# DVI.net
KiCad netlist of a schematic drawn in Altium Designer
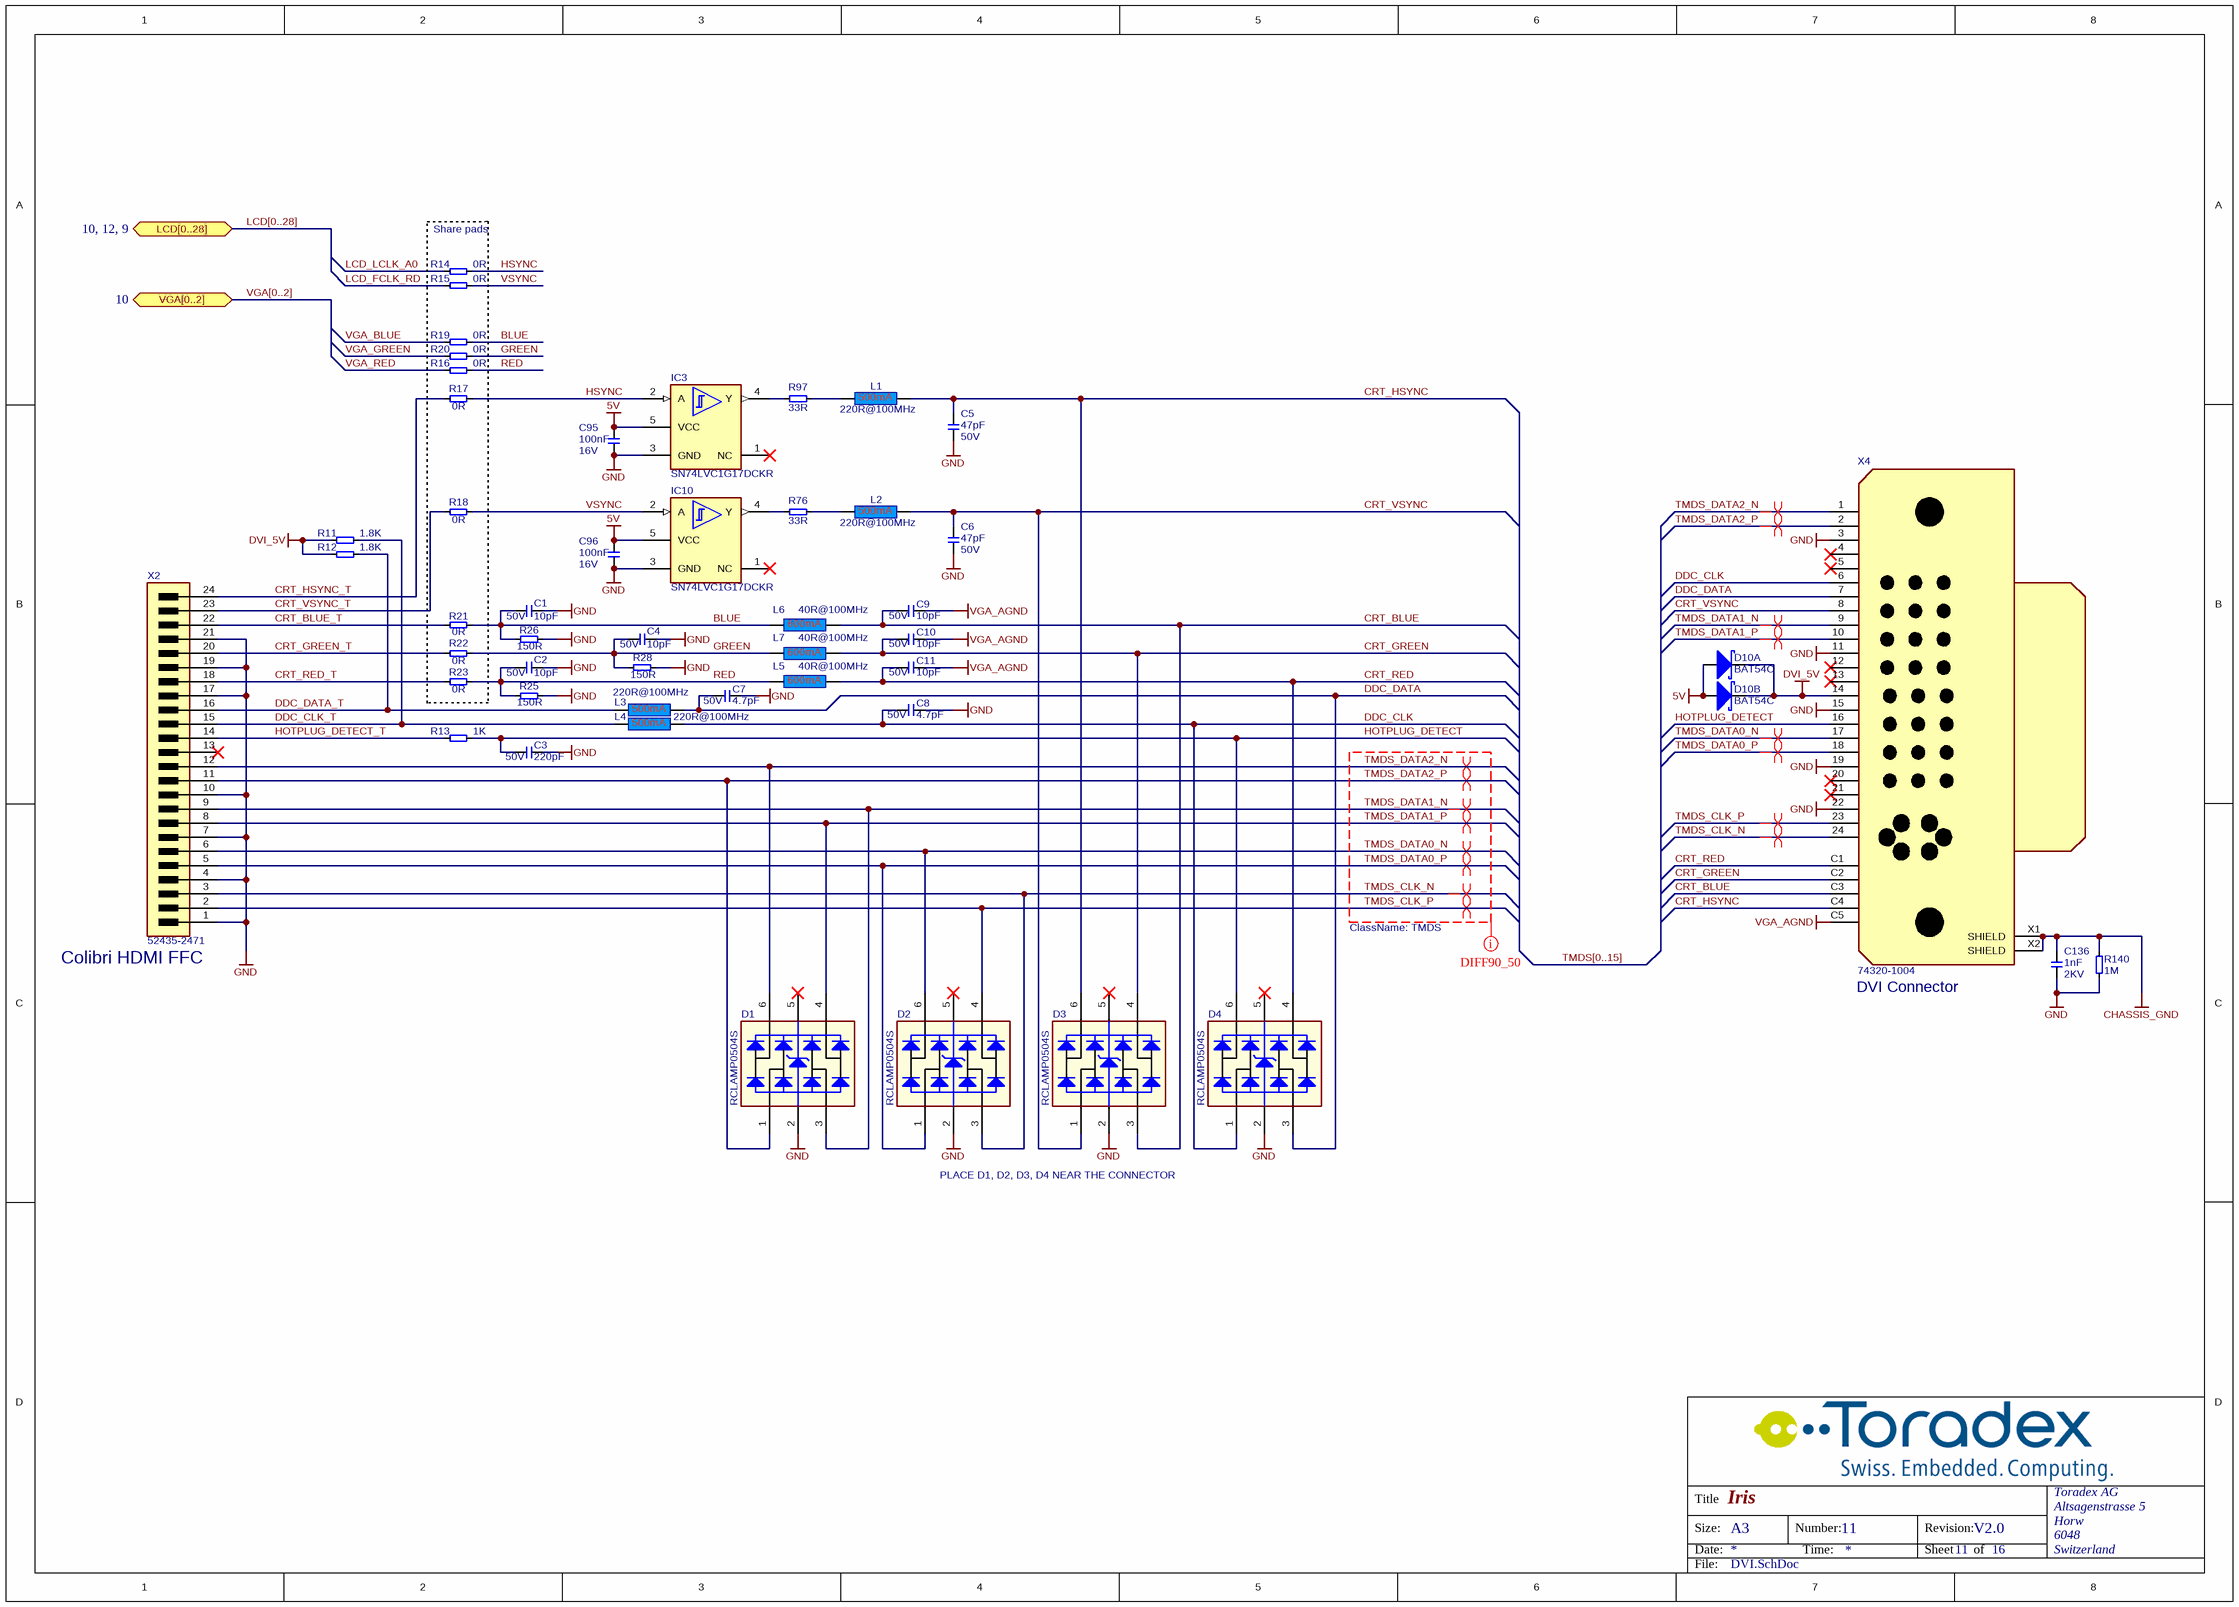
[diagram p0: DVI.SchDoc]

(export (version "E")
  (design (tool "Eeschema 10.0.6"))
  (components
    (comp (ref "C1")
      (value "10pF")
      (footprint "CAPC1005X60N")
      (description "Capacitor Ceramic NP0 10pF 50V 10% 0402")
      (fields (field (name "TOLERANCE") "10%") (field (name "RATING") "50V"))
      (libsource (lib "Iris") (part "C-NP0-10pF-50V-10%-0402"))
    )
    (comp (ref "C2")
      (value "10pF")
      (footprint "CAPC1005X60N")
      (description "Capacitor Ceramic NP0 10pF 50V 10% 0402")
      (fields (field (name "TOLERANCE") "10%") (field (name "RATING") "50V"))
      (libsource (lib "Iris") (part "C-NP0-10pF-50V-10%-0402"))
    )
    (comp (ref "C3")
      (value "220pF")
      (footprint "CAPC1005X60N")
      (description "Capacitor Ceramic X7R 220pF 50V 10% 0402")
      (fields (field (name "TOLERANCE") "10%") (field (name "RATING") "50V"))
      (libsource (lib "Iris") (part "C-X7R-220pF-50V-10%-0402"))
    )
    (comp (ref "C4")
      (value "10pF")
      (footprint "CAPC1005X60N")
      (description "Capacitor Ceramic NP0 10pF 50V 10% 0402")
      (fields (field (name "TOLERANCE") "10%") (field (name "RATING") "50V"))
      (libsource (lib "Iris") (part "C-NP0-10pF-50V-10%-0402"))
    )
    (comp (ref "C5")
      (value "47pF")
      (footprint "CAPC1005X60N")
      (description "Capacitor Ceramic NP0 47pF 50V 5% 0402")
      (fields (field (name "TOLERANCE") "5%") (field (name "RATING") "50V"))
      (libsource (lib "Iris") (part "C-NP0-47pF-50V-5%-0402"))
    )
    (comp (ref "C6")
      (value "47pF")
      (footprint "CAPC1005X60N")
      (description "Capacitor Ceramic NP0 47pF 50V 5% 0402")
      (fields (field (name "TOLERANCE") "5%") (field (name "RATING") "50V"))
      (libsource (lib "Iris") (part "C-NP0-47pF-50V-5%-0402"))
    )
    (comp (ref "C7")
      (value "4.7pF")
      (footprint "CAPC1005X60N")
      (description "Capacitor Ceramic NP0  4.7pF 50V 10% 0402")
      (fields (field (name "TOLERANCE") "10%") (field (name "RATING") "50V"))
      (libsource (lib "Iris") (part "C-NP0-4.7pF-50V-10%-0402"))
    )
    (comp (ref "C8")
      (value "4.7pF")
      (footprint "CAPC1005X60N")
      (description "Capacitor Ceramic NP0  4.7pF 50V 10% 0402")
      (fields (field (name "TOLERANCE") "10%") (field (name "RATING") "50V"))
      (libsource (lib "Iris") (part "C-NP0-4.7pF-50V-10%-0402"))
    )
    (comp (ref "C9")
      (value "10pF")
      (footprint "CAPC1005X60N")
      (description "Capacitor Ceramic NP0 10pF 50V 10% 0402")
      (fields (field (name "TOLERANCE") "10%") (field (name "RATING") "50V"))
      (libsource (lib "Iris") (part "C-NP0-10pF-50V-10%-0402"))
    )
    (comp (ref "C10")
      (value "10pF")
      (footprint "CAPC1005X60N")
      (description "Capacitor Ceramic NP0 10pF 50V 10% 0402")
      (fields (field (name "TOLERANCE") "10%") (field (name "RATING") "50V"))
      (libsource (lib "Iris") (part "C-NP0-10pF-50V-10%-0402"))
    )
    (comp (ref "C11")
      (value "10pF")
      (footprint "CAPC1005X60N")
      (description "Capacitor Ceramic NP0 10pF 50V 10% 0402")
      (fields (field (name "TOLERANCE") "10%") (field (name "RATING") "50V"))
      (libsource (lib "Iris") (part "C-NP0-10pF-50V-10%-0402"))
    )
    (comp (ref "C95")
      (value "100nF")
      (footprint "CAPC1005X60N")
      (description "Capacitor Ceramic X7R 100nF 16V 10% 0402")
      (fields (field (name "TOLERANCE") "10%") (field (name "RATING") "16V"))
      (libsource (lib "Iris") (part "C-X7R-100nF-16V-10%-0402"))
    )
    (comp (ref "C96")
      (value "100nF")
      (footprint "CAPC1005X60N")
      (description "Capacitor Ceramic X7R 100nF 16V 10% 0402")
      (fields (field (name "TOLERANCE") "10%") (field (name "RATING") "16V"))
      (libsource (lib "Iris") (part "C-X7R-100nF-16V-10%-0402"))
    )
    (comp (ref "C136")
      (value "1nF")
      (footprint "T_CAPC1206X180N")
      (description "Capacitor Ceramic X7R 1nF 2KV 10% 1206")
      (fields (field (name "TOLERANCE") "10%") (field (name "RATING") "2KV"))
      (libsource (lib "Iris") (part "C-X7R-1nF-2KV-10%-1206"))
    )
    (comp (ref "D1")
      (value "RCLAMP0504S")
      (footprint "T_SOT95P285X90-6N")
      (description "TVS Array low cap")
      (fields (field (name "MANUFACTURER PART NO.") "RCLAMP0504S"))
      (libsource (lib "Iris") (part "D-Semtech-RClamp0504S"))
    )
    (comp (ref "D2")
      (value "RCLAMP0504S")
      (footprint "T_SOT95P285X90-6N")
      (description "TVS Array low cap")
      (fields (field (name "MANUFACTURER PART NO.") "RCLAMP0504S"))
      (libsource (lib "Iris") (part "D-Semtech-RClamp0504S"))
    )
    (comp (ref "D3")
      (value "RCLAMP0504S")
      (footprint "T_SOT95P285X90-6N")
      (description "TVS Array low cap")
      (fields (field (name "MANUFACTURER PART NO.") "RCLAMP0504S"))
      (libsource (lib "Iris") (part "D-Semtech-RClamp0504S"))
    )
    (comp (ref "D4")
      (value "RCLAMP0504S")
      (footprint "T_SOT95P285X90-6N")
      (description "TVS Array low cap")
      (fields (field (name "MANUFACTURER PART NO.") "RCLAMP0504S"))
      (libsource (lib "Iris") (part "D-Semtech-RClamp0504S"))
    )
    (comp (ref "D10")
      (value "BAT54C")
      (footprint "SOT95P230X110-3N")
      (description "BAT54C Schottky Diode")
      (fields (field (name "MANUFACTURER PART NO.") "BAT54C"))
      (libsource (lib "Iris") (part "D-Philips-BAT54C-Schottky"))
    )
    (comp (ref "IC3")
      (value "SN74LVC1G17DCKR")
      (footprint "SOT65P210X110-5N")
      (description "Schmitt Trigger Buffer, SO-70 package")
      (fields (field (name "MANUFACTURER PART NO.") "SN74LVC1G17DCKR"))
      (libsource (lib "Iris") (part "IC-TI-SN74LVC1G17DCKR"))
    )
    (comp (ref "IC10")
      (value "SN74LVC1G17DCKR")
      (footprint "SOT65P210X110-5N")
      (description "Schmitt Trigger Buffer, SO-70 package")
      (fields (field (name "MANUFACTURER PART NO.") "SN74LVC1G17DCKR"))
      (libsource (lib "Iris") (part "IC-TI-SN74LVC1G17DCKR"))
    )
    (comp (ref "L1")
      (value "220R@100MHz")
      (footprint "INDC1005X55N")
      (description "Ferrite Bead, 220R@100MHz, 500mA, 0402 (1005 metric)")
      (fields (field (name "TOLERANCE") "25%"))
      (libsource (lib "Iris") (part "L-220R@100MHz-500mA-25%-0402"))
    )
    (comp (ref "L2")
      (value "220R@100MHz")
      (footprint "INDC1005X55N")
      (description "Ferrite Bead, 220R@100MHz, 500mA, 0402 (1005 metric)")
      (fields (field (name "TOLERANCE") "25%"))
      (libsource (lib "Iris") (part "L-220R@100MHz-500mA-25%-0402"))
    )
    (comp (ref "L3")
      (value "220R@100MHz")
      (footprint "INDC1005X55N")
      (description "Ferrite Bead, 220R@100MHz, 500mA, 0402 (1005 metric)")
      (fields (field (name "TOLERANCE") "25%"))
      (libsource (lib "Iris") (part "L-220R@100MHz-500mA-25%-0402"))
    )
    (comp (ref "L4")
      (value "220R@100MHz")
      (footprint "INDC1005X55N")
      (description "Ferrite Bead, 220R@100MHz, 500mA, 0402 (1005 metric)")
      (fields (field (name "TOLERANCE") "25%"))
      (libsource (lib "Iris") (part "L-220R@100MHz-500mA-25%-0402"))
    )
    (comp (ref "L5")
      (value "40R@100MHz")
      (footprint "INDC1608X95N")
      (description "40R@100MHz 600mA EMI FILTER")
      (fields (field (name "TOLERANCE") "25%") (field (name "MANUFACTURER PART NO.") "MMZ1608S400A"))
      (libsource (lib "Iris") (part "L-TDK-MMZ1608S400A-40R@100MHz-600mA-25%-0603"))
    )
    (comp (ref "L6")
      (value "40R@100MHz")
      (footprint "INDC1608X95N")
      (description "40R@100MHz 600mA EMI FILTER")
      (fields (field (name "TOLERANCE") "25%") (field (name "MANUFACTURER PART NO.") "MMZ1608S400A"))
      (libsource (lib "Iris") (part "L-TDK-MMZ1608S400A-40R@100MHz-600mA-25%-0603"))
    )
    (comp (ref "L7")
      (value "40R@100MHz")
      (footprint "INDC1608X95N")
      (description "40R@100MHz 600mA EMI FILTER")
      (fields (field (name "TOLERANCE") "25%") (field (name "MANUFACTURER PART NO.") "MMZ1608S400A"))
      (libsource (lib "Iris") (part "L-TDK-MMZ1608S400A-40R@100MHz-600mA-25%-0603"))
    )
    (comp (ref "R11")
      (value "1.8K")
      (footprint "RESC1005X40N")
      (description "Resistor 1.8 Kohm 63mW 5% 0402")
      (fields (field (name "TOLERANCE") "5%"))
      (libsource (lib "Iris") (part "R-1.8KR-63mW-5%-0402"))
    )
    (comp (ref "R12")
      (value "1.8K")
      (footprint "RESC1005X40N")
      (description "Resistor 1.8 Kohm 63mW 5% 0402")
      (fields (field (name "TOLERANCE") "5%"))
      (libsource (lib "Iris") (part "R-1.8KR-63mW-5%-0402"))
    )
    (comp (ref "R13")
      (value "1K")
      (footprint "RESC1005X40N")
      (description "Resistor 1 Kohm 63mW 5% 0402")
      (fields (field (name "TOLERANCE") "5%"))
      (libsource (lib "Iris") (part "R-1KR-63mW-5%-0402"))
    )
    (comp (ref "R14")
      (value "0R")
      (footprint "T_RESC0603X30N")
      (description "Resistor 0 ohm 63mW 5% 0603")
      (fields (field (name "TOLERANCE") "5%"))
      (libsource (lib "Iris") (part "R-0R-63mW-5%-0603"))
    )
    (comp (ref "R15")
      (value "0R")
      (footprint "T_RESC0603X30N")
      (description "Resistor 0 ohm 63mW 5% 0603")
      (fields (field (name "TOLERANCE") "5%"))
      (libsource (lib "Iris") (part "R-0R-63mW-5%-0603"))
    )
    (comp (ref "R16")
      (value "0R")
      (footprint "T_RESC0603X30N")
      (description "Resistor 0 ohm 63mW 5% 0603")
      (fields (field (name "TOLERANCE") "5%"))
      (libsource (lib "Iris") (part "R-0R-63mW-5%-0603"))
    )
    (comp (ref "R17")
      (value "0R")
      (footprint "T_RESC0603X30N")
      (description "Resistor 0 ohm 63mW 5% 0603")
      (fields (field (name "TOLERANCE") "5%"))
      (libsource (lib "Iris") (part "R-0R-63mW-5%-0603"))
    )
    (comp (ref "R18")
      (value "0R")
      (footprint "T_RESC0603X30N")
      (description "Resistor 0 ohm 63mW 5% 0603")
      (fields (field (name "TOLERANCE") "5%"))
      (libsource (lib "Iris") (part "R-0R-63mW-5%-0603"))
    )
    (comp (ref "R19")
      (value "0R")
      (footprint "T_RESC0603X30N")
      (description "Resistor 0 ohm 63mW 5% 0603")
      (fields (field (name "TOLERANCE") "5%"))
      (libsource (lib "Iris") (part "R-0R-63mW-5%-0603"))
    )
    (comp (ref "R20")
      (value "0R")
      (footprint "T_RESC0603X30N")
      (description "Resistor 0 ohm 63mW 5% 0603")
      (fields (field (name "TOLERANCE") "5%"))
      (libsource (lib "Iris") (part "R-0R-63mW-5%-0603"))
    )
    (comp (ref "R21")
      (value "0R")
      (footprint "T_RESC0603X30N")
      (description "Resistor 0 ohm 63mW 5% 0603")
      (fields (field (name "TOLERANCE") "5%"))
      (libsource (lib "Iris") (part "R-0R-63mW-5%-0603"))
    )
    (comp (ref "R22")
      (value "0R")
      (footprint "T_RESC0603X30N")
      (description "Resistor 0 ohm 63mW 5% 0603")
      (fields (field (name "TOLERANCE") "5%"))
      (libsource (lib "Iris") (part "R-0R-63mW-5%-0603"))
    )
    (comp (ref "R23")
      (value "0R")
      (footprint "T_RESC0603X30N")
      (description "Resistor 0 ohm 63mW 5% 0603")
      (fields (field (name "TOLERANCE") "5%"))
      (libsource (lib "Iris") (part "R-0R-63mW-5%-0603"))
    )
    (comp (ref "R25")
      (value "150R")
      (footprint "RESC1005X40N")
      (description "Resistor 150 ohm 63mW 5% 0402")
      (fields (field (name "TOLERANCE") "5%"))
      (libsource (lib "Iris") (part "R-150R-63mW-5%-0402"))
    )
    (comp (ref "R26")
      (value "150R")
      (footprint "RESC1005X40N")
      (description "Resistor 150 ohm 63mW 5% 0402")
      (fields (field (name "TOLERANCE") "5%"))
      (libsource (lib "Iris") (part "R-150R-63mW-5%-0402"))
    )
    (comp (ref "R28")
      (value "150R")
      (footprint "RESC1005X40N")
      (description "Resistor 150 ohm 63mW 5% 0402")
      (fields (field (name "TOLERANCE") "5%"))
      (libsource (lib "Iris") (part "R-150R-63mW-5%-0402"))
    )
    (comp (ref "R76")
      (value "33R")
      (footprint "RESC1005X40N")
      (description "Resistor 33 ohm 63mW 5% 0402")
      (fields (field (name "TOLERANCE") "5%"))
      (libsource (lib "Iris") (part "R-33R-63mW-5%-0402"))
    )
    (comp (ref "R97")
      (value "33R")
      (footprint "RESC1005X40N")
      (description "Resistor 33 ohm 63mW 5% 0402")
      (fields (field (name "TOLERANCE") "5%"))
      (libsource (lib "Iris") (part "R-33R-63mW-5%-0402"))
    )
    (comp (ref "R140")
      (value "1M")
      (footprint "T_RESC0603X30N")
      (description "Resistor 1 Mohm 63mW 5% 0603")
      (fields (field (name "TOLERANCE") "5%"))
      (libsource (lib "Iris") (part "R-1MR-63mW-5%-0603"))
    )
    (comp (ref "X2")
      (value "52435-2471")
      (footprint "T_MOLEX_52435-2471")
      (description "0.50mm Pitch FFC/FPC DVI Connector")
      (fields (field (name "MANUFACTURER PART NO.") "52435-2471"))
      (libsource (lib "Iris") (part "CON-Molex-52435-2471-24-0.5mm"))
    )
    (comp (ref "X4")
      (value "CON-Molex-74320-1004-31")
      (footprint "T_MOLEX_74320-1004")
      (description "DVI Connector")
      (fields (field (name "MANUFACTURER PART NO.") "74320-1004"))
      (libsource (lib "Iris") (part "CON-Molex-74320-1004-31"))
    )
  )
  (nets
    (net (code "49") (name "/BLUE") (class "Default")
      (node (ref "C1") (pin "1") (pinfunction "1_1") (pintype "passive"))
      (node (ref "L6") (pin "1") (pinfunction "1_1") (pintype "passive"))
      (node (ref "R19") (pin "1") (pinfunction "1_1") (pintype "passive"))
      (node (ref "R21") (pin "1") (pinfunction "1_1") (pintype "passive"))
      (node (ref "R26") (pin "1") (pinfunction "1_1") (pintype "passive"))
    )
    (net (code "50") (name "/CRT_BLUE") (class "Default")
      (node (ref "C9") (pin "1") (pinfunction "1_1") (pintype "passive"))
      (node (ref "D3") (pin "3") (pinfunction "3_3") (pintype "power_in"))
      (node (ref "L6") (pin "2") (pinfunction "2_2") (pintype "passive"))
      (node (ref "X4") (pin "C3") (pinfunction "CRT_BLUE_C3") (pintype "passive"))
    )
    (net (code "51") (name "/CRT_BLUE_T") (class "Default")
      (node (ref "R21") (pin "2") (pinfunction "2_2") (pintype "passive"))
      (node (ref "X2") (pin "22") (pinfunction "CRT_BLUE_22") (pintype "passive"))
    )
    (net (code "52") (name "/CRT_GREEN") (class "Default")
      (node (ref "C10") (pin "1") (pinfunction "1_1") (pintype "passive"))
      (node (ref "D3") (pin "4") (pinfunction "4_4") (pintype "power_in"))
      (node (ref "L7") (pin "2") (pinfunction "2_2") (pintype "passive"))
      (node (ref "X4") (pin "C2") (pinfunction "CRT_GREEN_C2") (pintype "passive"))
    )
    (net (code "53") (name "/CRT_GREEN_T") (class "Default")
      (node (ref "R22") (pin "2") (pinfunction "2_2") (pintype "passive"))
      (node (ref "X2") (pin "20") (pinfunction "CRT_GREEN_20") (pintype "passive"))
    )
    (net (code "54") (name "/CRT_HSYNC") (class "Default")
      (node (ref "C5") (pin "1") (pinfunction "1_1") (pintype "passive"))
      (node (ref "D3") (pin "6") (pinfunction "6_6") (pintype "power_in"))
      (node (ref "L1") (pin "2") (pinfunction "2_2") (pintype "passive"))
      (node (ref "X4") (pin "C4") (pinfunction "CRT_HSYNC_C4") (pintype "passive"))
    )
    (net (code "55") (name "/CRT_HSYNC_T") (class "Default")
      (node (ref "R17") (pin "1") (pinfunction "1_1") (pintype "passive"))
      (node (ref "X2") (pin "24") (pinfunction "CRT_HSYNC_24") (pintype "passive"))
    )
    (net (code "56") (name "/CRT_RED") (class "Default")
      (node (ref "C11") (pin "1") (pinfunction "1_1") (pintype "passive"))
      (node (ref "D4") (pin "4") (pinfunction "4_4") (pintype "power_in"))
      (node (ref "L5") (pin "2") (pinfunction "2_2") (pintype "passive"))
      (node (ref "X4") (pin "C1") (pinfunction "CRT_RED_C1") (pintype "passive"))
    )
    (net (code "57") (name "/CRT_RED_T") (class "Default")
      (node (ref "R23") (pin "2") (pinfunction "2_2") (pintype "passive"))
      (node (ref "X2") (pin "18") (pinfunction "CRT_RED_18") (pintype "passive"))
    )
    (net (code "58") (name "/CRT_VSYNC") (class "Default")
      (node (ref "C6") (pin "1") (pinfunction "1_1") (pintype "passive"))
      (node (ref "D3") (pin "1") (pinfunction "1_1") (pintype "power_in"))
      (node (ref "L2") (pin "2") (pinfunction "2_2") (pintype "passive"))
      (node (ref "X4") (pin "8") (pinfunction "CRT_VSYNC_8") (pintype "passive"))
    )
    (net (code "59") (name "/CRT_VSYNC_T") (class "Default")
      (node (ref "R18") (pin "1") (pinfunction "1_1") (pintype "passive"))
      (node (ref "X2") (pin "23") (pinfunction "CRT_VSYNC_23") (pintype "passive"))
    )
    (net (code "60") (name "/DDC_CLK") (class "Default")
      (node (ref "C8") (pin "1") (pinfunction "1_1") (pintype "passive"))
      (node (ref "D4") (pin "1") (pinfunction "1_1") (pintype "power_in"))
      (node (ref "L4") (pin "2") (pinfunction "2_2") (pintype "passive"))
      (node (ref "X4") (pin "6") (pinfunction "DDC_CLK_6") (pintype "passive"))
    )
    (net (code "61") (name "/DDC_CLK_T") (class "Default")
      (node (ref "L4") (pin "1") (pinfunction "1_1") (pintype "passive"))
      (node (ref "R11") (pin "1") (pinfunction "1_1") (pintype "passive"))
      (node (ref "X2") (pin "15") (pinfunction "DDC_CLK_15") (pintype "passive"))
    )
    (net (code "62") (name "/DDC_DATA") (class "Default")
      (node (ref "C7") (pin "1") (pinfunction "1_1") (pintype "passive"))
      (node (ref "D4") (pin "3") (pinfunction "3_3") (pintype "power_in"))
      (node (ref "L3") (pin "2") (pinfunction "2_2") (pintype "passive"))
      (node (ref "X4") (pin "7") (pinfunction "DDC_DATA_7") (pintype "passive"))
    )
    (net (code "63") (name "/DDC_DATA_T") (class "Default")
      (node (ref "L3") (pin "1") (pinfunction "1_1") (pintype "passive"))
      (node (ref "R12") (pin "1") (pinfunction "1_1") (pintype "passive"))
      (node (ref "X2") (pin "16") (pinfunction "DDC_DATA_16") (pintype "passive"))
    )
    (net (code "64") (name "/GREEN") (class "Default")
      (node (ref "C4") (pin "1") (pinfunction "1_1") (pintype "passive"))
      (node (ref "L7") (pin "1") (pinfunction "1_1") (pintype "passive"))
      (node (ref "R20") (pin "1") (pinfunction "1_1") (pintype "passive"))
      (node (ref "R22") (pin "1") (pinfunction "1_1") (pintype "passive"))
      (node (ref "R28") (pin "1") (pinfunction "1_1") (pintype "passive"))
    )
    (net (code "65") (name "/HOTPLUG_DETECT") (class "Default")
      (node (ref "C3") (pin "1") (pinfunction "1_1") (pintype "passive"))
      (node (ref "D4") (pin "6") (pinfunction "6_6") (pintype "power_in"))
      (node (ref "R13") (pin "2") (pinfunction "2_2") (pintype "passive"))
      (node (ref "X4") (pin "16") (pinfunction "HOTPLUG_DETECT_16") (pintype "passive"))
    )
    (net (code "66") (name "/HOTPLUG_DETECT_T") (class "Default")
      (node (ref "R13") (pin "1") (pinfunction "1_1") (pintype "passive"))
      (node (ref "X2") (pin "14") (pinfunction "HOTPLUG_DETECT_14") (pintype "passive"))
    )
    (net (code "67") (name "/HSYNC") (class "Default")
      (node (ref "IC3") (pin "2") (pinfunction "A_2") (pintype "input"))
      (node (ref "R14") (pin "2") (pinfunction "2_2") (pintype "passive"))
      (node (ref "R17") (pin "2") (pinfunction "2_2") (pintype "passive"))
    )
    (net (code "69") (name "/LCD_FCLK_RD") (class "Default")
      (node (ref "R15") (pin "1") (pinfunction "1_1") (pintype "passive"))
    )
    (net (code "70") (name "/LCD_LCLK_A0") (class "Default")
      (node (ref "R14") (pin "1") (pinfunction "1_1") (pintype "passive"))
    )
    (net (code "71") (name "/RED") (class "Default")
      (node (ref "C2") (pin "1") (pinfunction "1_1") (pintype "passive"))
      (node (ref "L5") (pin "1") (pinfunction "1_1") (pintype "passive"))
      (node (ref "R16") (pin "1") (pinfunction "1_1") (pintype "passive"))
      (node (ref "R23") (pin "1") (pinfunction "1_1") (pintype "passive"))
      (node (ref "R25") (pin "1") (pinfunction "1_1") (pintype "passive"))
    )
    (net (code "73") (name "/TMDS_CLK_N") (class "Default")
      (node (ref "D2") (pin "3") (pinfunction "3_3") (pintype "power_in"))
      (node (ref "X2") (pin "3") (pinfunction "TMDS_CLK_N_3") (pintype "passive"))
      (node (ref "X4") (pin "24") (pinfunction "TMDS_CLK_N_24") (pintype "passive"))
    )
    (net (code "74") (name "/TMDS_CLK_P") (class "Default")
      (node (ref "D2") (pin "4") (pinfunction "4_4") (pintype "power_in"))
      (node (ref "X2") (pin "2") (pinfunction "TMDS_CLK_P_2") (pintype "passive"))
      (node (ref "X4") (pin "23") (pinfunction "TMDS_CLK_P_23") (pintype "passive"))
    )
    (net (code "75") (name "/TMDS_DATA0_N") (class "Default")
      (node (ref "D2") (pin "6") (pinfunction "6_6") (pintype "power_in"))
      (node (ref "X2") (pin "6") (pinfunction "TMDS_DATA0_N_6") (pintype "passive"))
      (node (ref "X4") (pin "17") (pinfunction "TMDS_DATA0_N_17") (pintype "passive"))
    )
    (net (code "76") (name "/TMDS_DATA0_P") (class "Default")
      (node (ref "D2") (pin "1") (pinfunction "1_1") (pintype "power_in"))
      (node (ref "X2") (pin "5") (pinfunction "TMDS_DATA0_P_5") (pintype "passive"))
      (node (ref "X4") (pin "18") (pinfunction "TMDS_DATA0_P_18") (pintype "passive"))
    )
    (net (code "77") (name "/TMDS_DATA1_N") (class "Default")
      (node (ref "D1") (pin "3") (pinfunction "3_3") (pintype "power_in"))
      (node (ref "X2") (pin "9") (pinfunction "TMDS_DATA1_N_9") (pintype "passive"))
      (node (ref "X4") (pin "9") (pinfunction "TMDS_DATA1_N_9") (pintype "passive"))
    )
    (net (code "78") (name "/TMDS_DATA1_P") (class "Default")
      (node (ref "D1") (pin "4") (pinfunction "4_4") (pintype "power_in"))
      (node (ref "X2") (pin "8") (pinfunction "TMDS_DATA1_P_8") (pintype "passive"))
      (node (ref "X4") (pin "10") (pinfunction "TMDS_DATA1_P_10") (pintype "passive"))
    )
    (net (code "79") (name "/TMDS_DATA2_N") (class "Default")
      (node (ref "D1") (pin "6") (pinfunction "6_6") (pintype "power_in"))
      (node (ref "X2") (pin "12") (pinfunction "TMDS_DATA2_N_12") (pintype "passive"))
      (node (ref "X4") (pin "1") (pinfunction "TMDS_DATA2_N_1") (pintype "passive"))
    )
    (net (code "80") (name "/TMDS_DATA2_P") (class "Default")
      (node (ref "D1") (pin "1") (pinfunction "1_1") (pintype "power_in"))
      (node (ref "X2") (pin "11") (pinfunction "TMDS_DATA2_P_11") (pintype "passive"))
      (node (ref "X4") (pin "2") (pinfunction "TMDS_DATA2_P_2") (pintype "passive"))
    )
    (net (code "82") (name "/VGA_BLUE") (class "Default")
      (node (ref "R19") (pin "2") (pinfunction "2_2") (pintype "passive"))
    )
    (net (code "83") (name "/VGA_GREEN") (class "Default")
      (node (ref "R20") (pin "2") (pinfunction "2_2") (pintype "passive"))
    )
    (net (code "84") (name "/VGA_RED") (class "Default")
      (node (ref "R16") (pin "2") (pinfunction "2_2") (pintype "passive"))
    )
    (net (code "85") (name "/VSYNC") (class "Default")
      (node (ref "IC10") (pin "2") (pinfunction "A_2") (pintype "input"))
      (node (ref "R15") (pin "2") (pinfunction "2_2") (pintype "passive"))
      (node (ref "R18") (pin "2") (pinfunction "2_2") (pintype "passive"))
    )
    (net (code "86") (name "5V") (class "Default")
      (node (ref "C95") (pin "2") (pinfunction "2_2") (pintype "passive"))
      (node (ref "C96") (pin "2") (pinfunction "2_2") (pintype "passive"))
      (node (ref "D10") (pin "1") (pinfunction "1_1") (pintype "passive"))
      (node (ref "D10") (pin "2") (pinfunction "2_2") (pintype "passive"))
      (node (ref "IC10") (pin "5") (pinfunction "VCC_5") (pintype "power_in"))
      (node (ref "IC3") (pin "5") (pinfunction "VCC_5") (pintype "power_in"))
    )
    (net (code "87") (name "CHASSIS_GND") (class "Default")
      (node (ref "C136") (pin "2") (pinfunction "2_2") (pintype "passive"))
      (node (ref "R140") (pin "2") (pinfunction "2_2") (pintype "passive"))
      (node (ref "X4") (pin "X1") (pinfunction "SHIELD_X1") (pintype "passive"))
      (node (ref "X4") (pin "X2") (pinfunction "SHIELD_X2") (pintype "passive"))
    )
    (net (code "88") (name "DVI_5V") (class "Default")
      (node (ref "D10") (pin "3") (pinfunction "3_3") (pintype "passive"))
      (node (ref "R11") (pin "2") (pinfunction "2_2") (pintype "passive"))
      (node (ref "R12") (pin "2") (pinfunction "2_2") (pintype "passive"))
      (node (ref "X4") (pin "14") (pinfunction "VDD_DVI_14") (pintype "passive"))
    )
    (net (code "89") (name "GND") (class "Default")
      (node (ref "C1") (pin "2") (pinfunction "2_2") (pintype "passive"))
      (node (ref "C136") (pin "1") (pinfunction "1_1") (pintype "passive"))
      (node (ref "C2") (pin "2") (pinfunction "2_2") (pintype "passive"))
      (node (ref "C3") (pin "2") (pinfunction "2_2") (pintype "passive"))
      (node (ref "C4") (pin "2") (pinfunction "2_2") (pintype "passive"))
      (node (ref "C5") (pin "2") (pinfunction "2_2") (pintype "passive"))
      (node (ref "C6") (pin "2") (pinfunction "2_2") (pintype "passive"))
      (node (ref "C7") (pin "2") (pinfunction "2_2") (pintype "passive"))
      (node (ref "C8") (pin "2") (pinfunction "2_2") (pintype "passive"))
      (node (ref "C95") (pin "1") (pinfunction "1_1") (pintype "passive"))
      (node (ref "C96") (pin "1") (pinfunction "1_1") (pintype "passive"))
      (node (ref "D1") (pin "2") (pinfunction "2_2") (pintype "power_in"))
      (node (ref "D2") (pin "2") (pinfunction "2_2") (pintype "power_in"))
      (node (ref "D3") (pin "2") (pinfunction "2_2") (pintype "power_in"))
      (node (ref "D4") (pin "2") (pinfunction "2_2") (pintype "power_in"))
      (node (ref "IC10") (pin "3") (pinfunction "GND_3") (pintype "power_in"))
      (node (ref "IC3") (pin "3") (pinfunction "GND_3") (pintype "power_in"))
      (node (ref "R140") (pin "1") (pinfunction "1_1") (pintype "passive"))
      (node (ref "R25") (pin "2") (pinfunction "2_2") (pintype "passive"))
      (node (ref "R26") (pin "2") (pinfunction "2_2") (pintype "passive"))
      (node (ref "R28") (pin "2") (pinfunction "2_2") (pintype "passive"))
      (node (ref "X2") (pin "1") (pinfunction "GND_1") (pintype "passive"))
      (node (ref "X2") (pin "10") (pinfunction "GND_10") (pintype "passive"))
      (node (ref "X2") (pin "17") (pinfunction "GND_17") (pintype "passive"))
      (node (ref "X2") (pin "19") (pinfunction "GND_19") (pintype "passive"))
      (node (ref "X2") (pin "21") (pinfunction "GND_21") (pintype "passive"))
      (node (ref "X2") (pin "4") (pinfunction "GND_4") (pintype "passive"))
      (node (ref "X2") (pin "7") (pinfunction "GND_7") (pintype "passive"))
      (node (ref "X4") (pin "11") (pinfunction "GND_11") (pintype "passive"))
      (node (ref "X4") (pin "15") (pinfunction "GND_15") (pintype "passive"))
      (node (ref "X4") (pin "19") (pinfunction "GND_19") (pintype "passive"))
      (node (ref "X4") (pin "22") (pinfunction "GND_22") (pintype "passive"))
      (node (ref "X4") (pin "3") (pinfunction "GND_3") (pintype "passive"))
    )
    (net (code "90") (name "Net-(IC3-Y)") (class "Default")
      (node (ref "IC3") (pin "4") (pinfunction "Y_4") (pintype "output"))
      (node (ref "R97") (pin "1") (pinfunction "1_1") (pintype "passive"))
    )
    (net (code "91") (name "Net-(IC10-Y)") (class "Default")
      (node (ref "IC10") (pin "4") (pinfunction "Y_4") (pintype "output"))
      (node (ref "R76") (pin "1") (pinfunction "1_1") (pintype "passive"))
    )
    (net (code "92") (name "Net-(L1-Pad1)") (class "Default")
      (node (ref "L1") (pin "1") (pinfunction "1_1") (pintype "passive"))
      (node (ref "R97") (pin "2") (pinfunction "2_2") (pintype "passive"))
    )
    (net (code "93") (name "Net-(L2-Pad1)") (class "Default")
      (node (ref "L2") (pin "1") (pinfunction "1_1") (pintype "passive"))
      (node (ref "R76") (pin "2") (pinfunction "2_2") (pintype "passive"))
    )
    (net (code "94") (name "VGA_AGND") (class "Default")
      (node (ref "C10") (pin "2") (pinfunction "2_2") (pintype "passive"))
      (node (ref "C11") (pin "2") (pinfunction "2_2") (pintype "passive"))
      (node (ref "C9") (pin "2") (pinfunction "2_2") (pintype "passive"))
      (node (ref "X4") (pin "C5") (pinfunction "GND_C5") (pintype "passive"))
    )
    (net (code "95") (name "unconnected-(D1-Pad5)") (class "Default")
      (node (ref "D1") (pin "5") (pinfunction "5_5") (pintype "power_in+no_connect"))
    )
    (net (code "96") (name "unconnected-(D2-Pad5)") (class "Default")
      (node (ref "D2") (pin "5") (pinfunction "5_5") (pintype "power_in+no_connect"))
    )
    (net (code "97") (name "unconnected-(D3-Pad5)") (class "Default")
      (node (ref "D3") (pin "5") (pinfunction "5_5") (pintype "power_in+no_connect"))
    )
    (net (code "98") (name "unconnected-(D4-Pad5)") (class "Default")
      (node (ref "D4") (pin "5") (pinfunction "5_5") (pintype "power_in+no_connect"))
    )
    (net (code "99") (name "unconnected-(IC3-NC-Pad1)") (class "Default")
      (node (ref "IC3") (pin "1") (pinfunction "NC_1") (pintype "passive+no_connect"))
    )
    (net (code "100") (name "unconnected-(IC10-NC-Pad1)") (class "Default")
      (node (ref "IC10") (pin "1") (pinfunction "NC_1") (pintype "passive+no_connect"))
    )
    (net (code "101") (name "unconnected-(X2-VDD-Pad13)") (class "Default")
      (node (ref "X2") (pin "13") (pinfunction "VDD_13") (pintype "passive+no_connect"))
    )
    (net (code "102") (name "unconnected-(X4-TMDS_DATA3_N-Pad12)") (class "Default")
      (node (ref "X4") (pin "12") (pinfunction "TMDS_DATA3_N_12") (pintype "passive+no_connect"))
    )
    (net (code "103") (name "unconnected-(X4-TMDS_DATA3_P-Pad13)") (class "Default")
      (node (ref "X4") (pin "13") (pinfunction "TMDS_DATA3_P_13") (pintype "passive+no_connect"))
    )
    (net (code "104") (name "unconnected-(X4-TMDS_DATA4_N-Pad4)") (class "Default")
      (node (ref "X4") (pin "4") (pinfunction "TMDS_DATA4_N_4") (pintype "passive+no_connect"))
    )
    (net (code "105") (name "unconnected-(X4-TMDS_DATA4_P-Pad5)") (class "Default")
      (node (ref "X4") (pin "5") (pinfunction "TMDS_DATA4_P_5") (pintype "passive+no_connect"))
    )
    (net (code "106") (name "unconnected-(X4-TMDS_DATA5_N-Pad20)") (class "Default")
      (node (ref "X4") (pin "20") (pinfunction "TMDS_DATA5_N_20") (pintype "passive+no_connect"))
    )
    (net (code "107") (name "unconnected-(X4-TMDS_DATA5_P-Pad21)") (class "Default")
      (node (ref "X4") (pin "21") (pinfunction "TMDS_DATA5_P_21") (pintype "passive+no_connect"))
    )
  )
)
